# fmc-interposer.net
KiCad netlist of a schematic drawn in Altium Designer
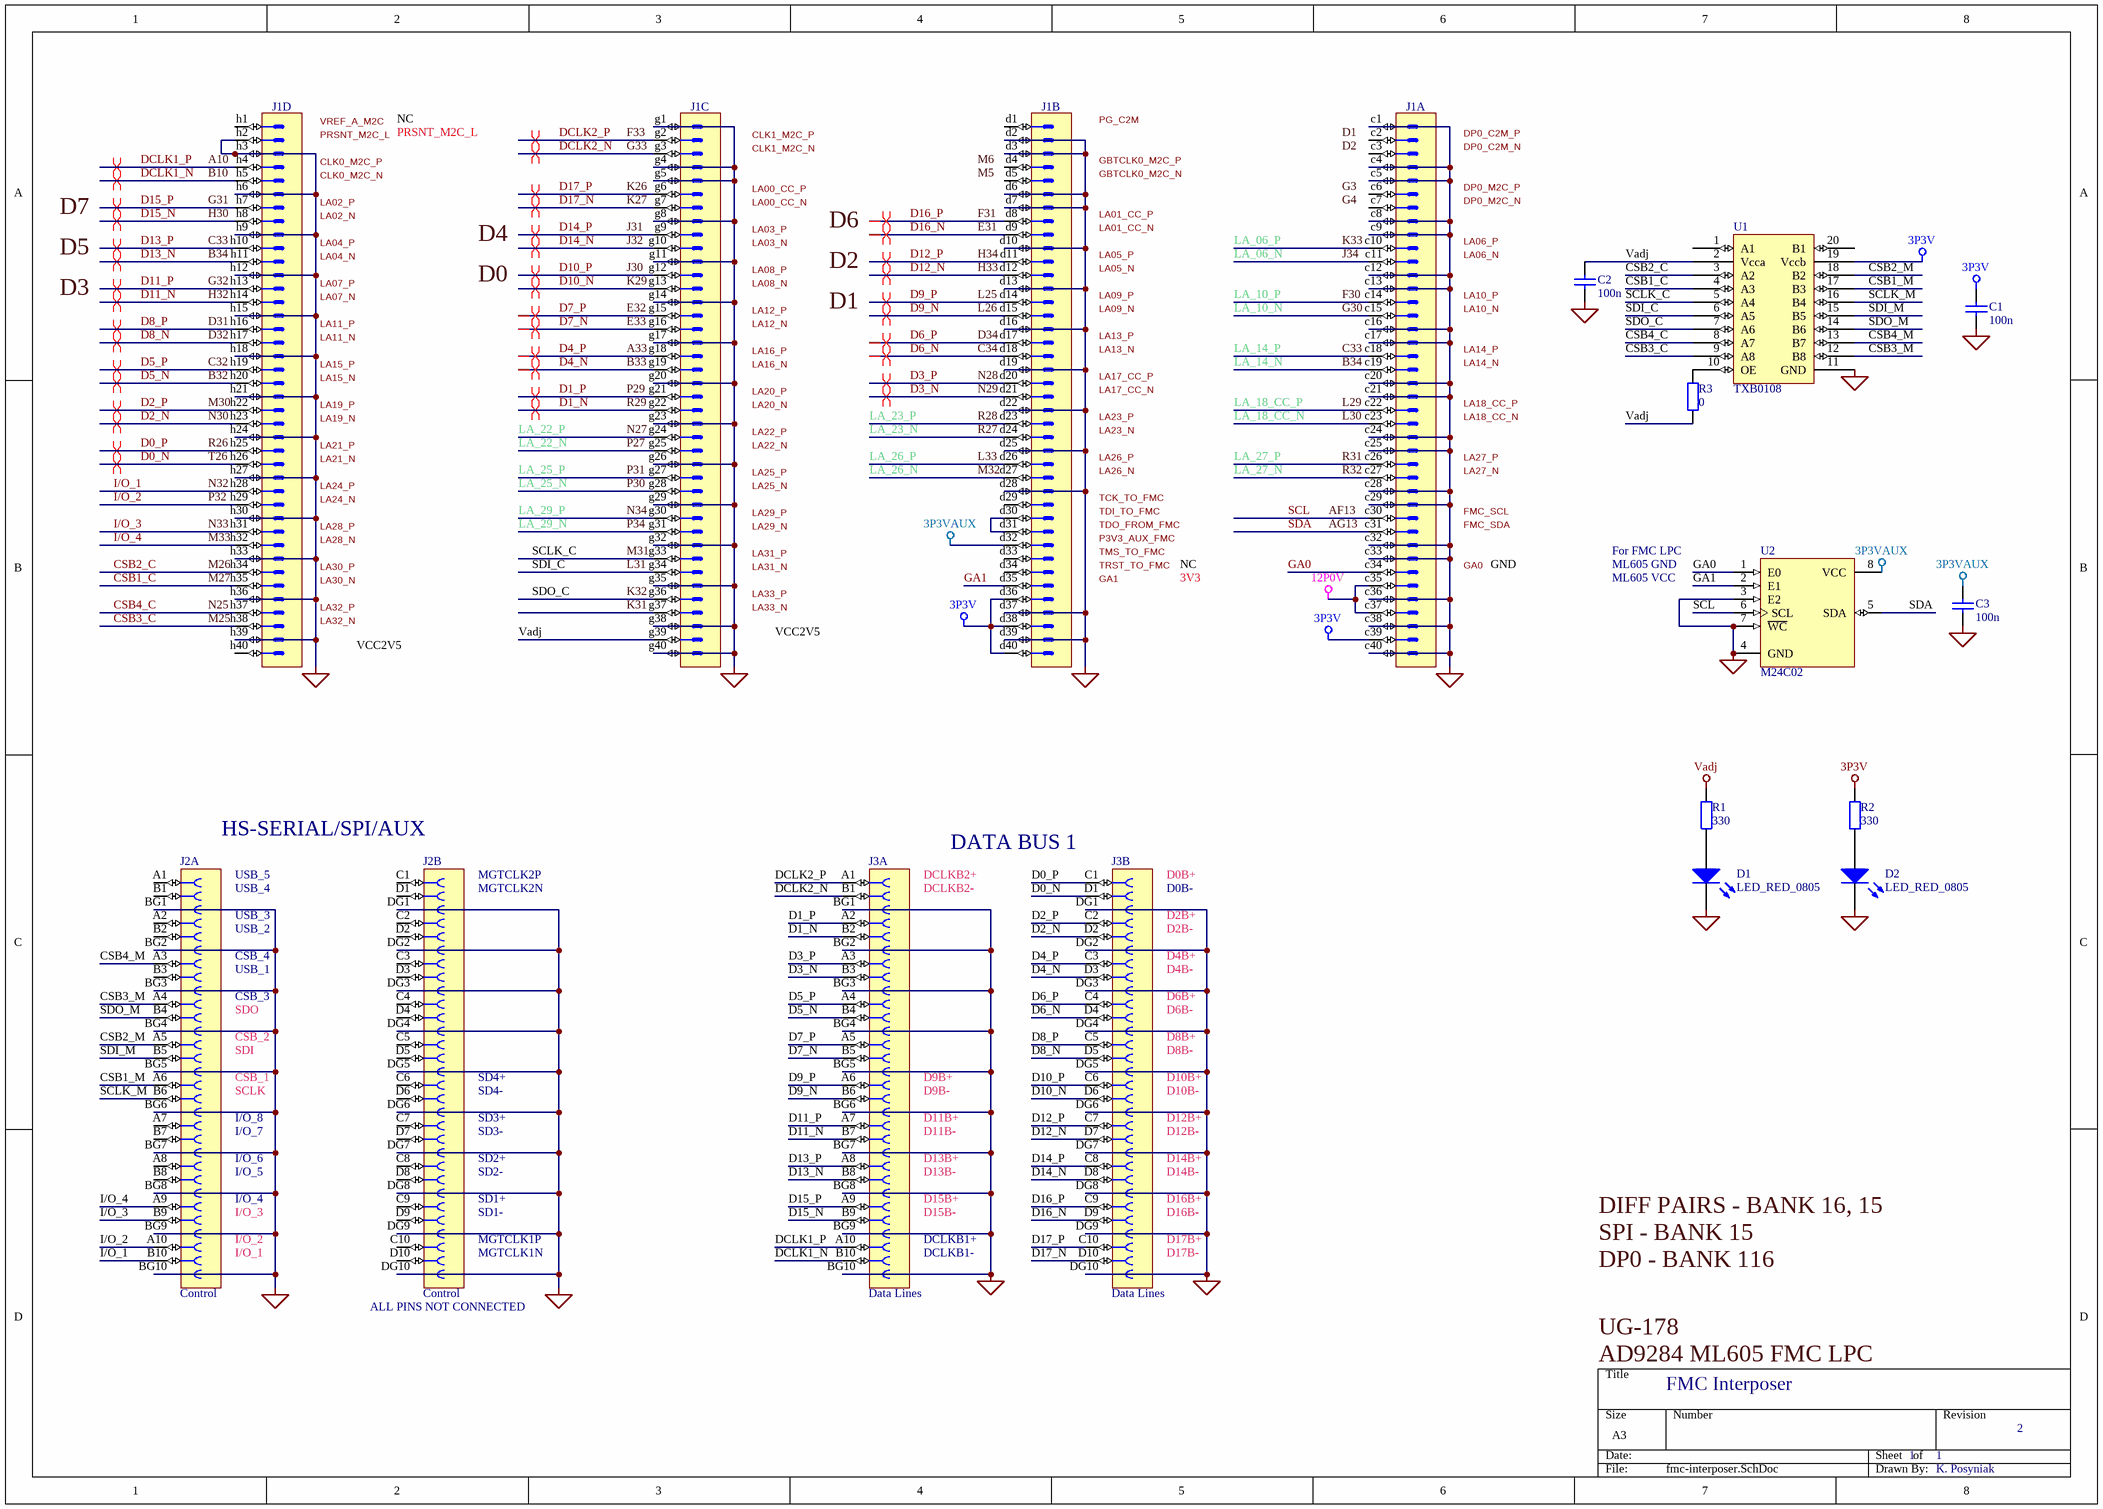
[diagram p0: fmc-interposer.SchDoc]

(export (version "E")
  (design (tool "Eeschema 10.0.6"))
  (components
    (comp (ref "C1")
      (value "100n")
      (footprint "capc1608n")
      (description "Capacitor")
      (fields (field (name "PUBLISHER") "Altium Limited"))
      (libsource (lib "Miscellaneous Devices") (part "Cap"))
    )
    (comp (ref "C2")
      (value "100n")
      (footprint "capc1608n")
      (description "Capacitor")
      (fields (field (name "PUBLISHER") "Altium Limited"))
      (libsource (lib "Miscellaneous Devices") (part "Cap"))
    )
    (comp (ref "C3")
      (value "100n")
      (footprint "capc1608n")
      (description "Capacitor")
      (fields (field (name "PUBLISHER") "Altium Limited"))
      (libsource (lib "Miscellaneous Devices") (part "Cap"))
    )
    (comp (ref "D1")
      (value "LED_RED_0805")
      (footprint "2.0X1.25X0.8")
      (description "Blue Surface Mount Chip LED, Blue")
      (fields (field (name "PUBLISHER") "Altium Limited"))
      (libsource (lib "Agilent Optoelectronic LED") (part "HSMB-C170"))
    )
    (comp (ref "D2")
      (value "LED_RED_0805")
      (footprint "2.0X1.25X0.8")
      (description "Blue Surface Mount Chip LED, Blue")
      (fields (field (name "PUBLISHER") "Altium Limited"))
      (libsource (lib "Agilent Optoelectronic LED") (part "HSMB-C170"))
    )
    (comp (ref "J1")
      (value "VITA 57")
      (footprint "SAMTEC_ASP-127797-01")
      (description "Connector VITA 57, 160 Male contacts in 4 row cdgh")
      (fields
        (field (name "PART NUMBER") "SAMTEC_ASP-127797-01")
        (field (name "MANUFACTURER") "SAMTEC")
        (field (name "AUTHOR") "CERN DEM JLC")
      )
      (libsource (lib "EDA-02408-V1") (part "Connector VITA 57 160 Male (cdgh)"))
    )
    (comp (ref "J2")
      (value "Control")
      (footprint "Analog_Conn2")
      (libsource (lib "kpos-sch") (part "Analog_Conn2"))
    )
    (comp (ref "J3")
      (value "Data Lines")
      (footprint "Analog_Conn2")
      (libsource (lib "kpos-sch") (part "Analog_Conn2"))
    )
    (comp (ref "R1")
      (value "330")
      (description "Resistor")
      (fields (field (name "PUBLISHER") "Altium Limited"))
      (libsource (lib "") (part "Res2_1"))
    )
    (comp (ref "R2")
      (value "330")
      (description "Resistor")
      (fields (field (name "PUBLISHER") "Altium Limited"))
      (libsource (lib "") (part "Res2_1"))
    )
    (comp (ref "R3")
      (value "0")
      (description "Resistor")
      (fields (field (name "PUBLISHER") "Altium Limited"))
      (libsource (lib "Miscellaneous Devices") (part "Res2"))
    )
    (comp (ref "U1") (value "TXB0108") (footprint "TSSOP20") (libsource (lib "kpos-sch") (part "TXB0108")))
    (comp (ref "U2")
      (value "M24C02")
      (footprint "SOP8_N")
      (description "2Kbit Serial I˛C Bus EEPROM")
      (fields (field (name "PUBLISHER") "Altium Limited"))
      (libsource (lib "ST Memory EEPROM Serial") (part "M24C02MN6"))
    )
  )
  (nets
    (net (code "1") (name "/CSB1_C") (class "Default")
      (node (ref "J1") (pin "h35") (pinfunction "h35_h35") (pintype "bidirectional"))
      (node (ref "U1") (pin "4") (pinfunction "A3_4") (pintype "bidirectional"))
    )
    (net (code "2") (name "/CSB1_M") (class "Default")
      (node (ref "J2") (pin "A6") (pinfunction "A6_A6") (pintype "bidirectional"))
      (node (ref "U1") (pin "17") (pinfunction "B3_17") (pintype "bidirectional"))
    )
    (net (code "3") (name "/CSB2_C") (class "Default")
      (node (ref "J1") (pin "h34") (pinfunction "h34_h34") (pintype "bidirectional"))
      (node (ref "U1") (pin "3") (pinfunction "A2_3") (pintype "bidirectional"))
    )
    (net (code "4") (name "/CSB2_M") (class "Default")
      (node (ref "J2") (pin "A5") (pinfunction "A5_A5") (pintype "bidirectional"))
      (node (ref "U1") (pin "18") (pinfunction "B2_18") (pintype "bidirectional"))
    )
    (net (code "5") (name "/CSB3_C") (class "Default")
      (node (ref "J1") (pin "h38") (pinfunction "h38_h38") (pintype "bidirectional"))
      (node (ref "U1") (pin "9") (pinfunction "A8_9") (pintype "bidirectional"))
    )
    (net (code "6") (name "/CSB3_M") (class "Default")
      (node (ref "J2") (pin "A4") (pinfunction "A4_A4") (pintype "bidirectional"))
      (node (ref "U1") (pin "12") (pinfunction "B8_12") (pintype "bidirectional"))
    )
    (net (code "7") (name "/CSB4_C") (class "Default")
      (node (ref "J1") (pin "h37") (pinfunction "h37_h37") (pintype "bidirectional"))
      (node (ref "U1") (pin "8") (pinfunction "A7_8") (pintype "bidirectional"))
    )
    (net (code "8") (name "/CSB4_M") (class "Default")
      (node (ref "J2") (pin "A3") (pinfunction "A3_A3") (pintype "bidirectional"))
      (node (ref "U1") (pin "13") (pinfunction "B7_13") (pintype "bidirectional"))
    )
    (net (code "9") (name "/D0_N") (class "Default")
      (node (ref "J1") (pin "h26") (pinfunction "h26_h26") (pintype "bidirectional"))
      (node (ref "J3") (pin "D1") (pinfunction "D1_D1") (pintype "bidirectional"))
    )
    (net (code "10") (name "/D0_P") (class "Default")
      (node (ref "J1") (pin "h25") (pinfunction "h25_h25") (pintype "bidirectional"))
      (node (ref "J3") (pin "C1") (pinfunction "C1_C1") (pintype "bidirectional"))
    )
    (net (code "11") (name "/D1_N") (class "Default")
      (node (ref "J1") (pin "g22") (pinfunction "g22_g22") (pintype "bidirectional"))
      (node (ref "J3") (pin "B2") (pinfunction "B2_B2") (pintype "bidirectional"))
    )
    (net (code "12") (name "/D1_P") (class "Default")
      (node (ref "J1") (pin "g21") (pinfunction "g21_g21") (pintype "bidirectional"))
      (node (ref "J3") (pin "A2") (pinfunction "A2_A2") (pintype "bidirectional"))
    )
    (net (code "13") (name "/D2_N") (class "Default")
      (node (ref "J1") (pin "h23") (pinfunction "h23_h23") (pintype "bidirectional"))
      (node (ref "J3") (pin "D2") (pinfunction "D2_D2") (pintype "bidirectional"))
    )
    (net (code "14") (name "/D2_P") (class "Default")
      (node (ref "J1") (pin "h22") (pinfunction "h22_h22") (pintype "bidirectional"))
      (node (ref "J3") (pin "C2") (pinfunction "C2_C2") (pintype "bidirectional"))
    )
    (net (code "15") (name "/D3_N") (class "Default")
      (node (ref "J1") (pin "d21") (pinfunction "d21_d21") (pintype "bidirectional"))
      (node (ref "J3") (pin "B3") (pinfunction "B3_B3") (pintype "bidirectional"))
    )
    (net (code "16") (name "/D3_P") (class "Default")
      (node (ref "J1") (pin "d20") (pinfunction "d20_d20") (pintype "bidirectional"))
      (node (ref "J3") (pin "A3") (pinfunction "A3_A3") (pintype "bidirectional"))
    )
    (net (code "17") (name "/D4_N") (class "Default")
      (node (ref "J1") (pin "g19") (pinfunction "g19_g19") (pintype "bidirectional"))
      (node (ref "J3") (pin "D3") (pinfunction "D3_D3") (pintype "bidirectional"))
    )
    (net (code "18") (name "/D4_P") (class "Default")
      (node (ref "J1") (pin "g18") (pinfunction "g18_g18") (pintype "bidirectional"))
      (node (ref "J3") (pin "C3") (pinfunction "C3_C3") (pintype "bidirectional"))
    )
    (net (code "19") (name "/D5_N") (class "Default")
      (node (ref "J1") (pin "h20") (pinfunction "h20_h20") (pintype "bidirectional"))
      (node (ref "J3") (pin "B4") (pinfunction "B4_B4") (pintype "bidirectional"))
    )
    (net (code "20") (name "/D5_P") (class "Default")
      (node (ref "J1") (pin "h19") (pinfunction "h19_h19") (pintype "bidirectional"))
      (node (ref "J3") (pin "A4") (pinfunction "A4_A4") (pintype "bidirectional"))
    )
    (net (code "21") (name "/D6_N") (class "Default")
      (node (ref "J1") (pin "d18") (pinfunction "d18_d18") (pintype "bidirectional"))
      (node (ref "J3") (pin "D4") (pinfunction "D4_D4") (pintype "bidirectional"))
    )
    (net (code "22") (name "/D6_P") (class "Default")
      (node (ref "J1") (pin "d17") (pinfunction "d17_d17") (pintype "bidirectional"))
      (node (ref "J3") (pin "C4") (pinfunction "C4_C4") (pintype "bidirectional"))
    )
    (net (code "23") (name "/D7_N") (class "Default")
      (node (ref "J1") (pin "g16") (pinfunction "g16_g16") (pintype "bidirectional"))
      (node (ref "J3") (pin "B5") (pinfunction "B5_B5") (pintype "bidirectional"))
    )
    (net (code "24") (name "/D7_P") (class "Default")
      (node (ref "J1") (pin "g15") (pinfunction "g15_g15") (pintype "bidirectional"))
      (node (ref "J3") (pin "A5") (pinfunction "A5_A5") (pintype "bidirectional"))
    )
    (net (code "25") (name "/D8_N") (class "Default")
      (node (ref "J1") (pin "h17") (pinfunction "h17_h17") (pintype "bidirectional"))
      (node (ref "J3") (pin "D5") (pinfunction "D5_D5") (pintype "bidirectional"))
    )
    (net (code "26") (name "/D8_P") (class "Default")
      (node (ref "J1") (pin "h16") (pinfunction "h16_h16") (pintype "bidirectional"))
      (node (ref "J3") (pin "C5") (pinfunction "C5_C5") (pintype "bidirectional"))
    )
    (net (code "27") (name "/D9_N") (class "Default")
      (node (ref "J1") (pin "d15") (pinfunction "d15_d15") (pintype "bidirectional"))
      (node (ref "J3") (pin "B6") (pinfunction "B6_B6") (pintype "bidirectional"))
    )
    (net (code "28") (name "/D9_P") (class "Default")
      (node (ref "J1") (pin "d14") (pinfunction "d14_d14") (pintype "bidirectional"))
      (node (ref "J3") (pin "A6") (pinfunction "A6_A6") (pintype "bidirectional"))
    )
    (net (code "29") (name "/D10_N") (class "Default")
      (node (ref "J1") (pin "g13") (pinfunction "g13_g13") (pintype "bidirectional"))
      (node (ref "J3") (pin "D6") (pinfunction "D6_D6") (pintype "bidirectional"))
    )
    (net (code "30") (name "/D10_P") (class "Default")
      (node (ref "J1") (pin "g12") (pinfunction "g12_g12") (pintype "bidirectional"))
      (node (ref "J3") (pin "C6") (pinfunction "C6_C6") (pintype "bidirectional"))
    )
    (net (code "31") (name "/D11_N") (class "Default")
      (node (ref "J1") (pin "h14") (pinfunction "h14_h14") (pintype "bidirectional"))
      (node (ref "J3") (pin "B7") (pinfunction "B7_B7") (pintype "bidirectional"))
    )
    (net (code "32") (name "/D11_P") (class "Default")
      (node (ref "J1") (pin "h13") (pinfunction "h13_h13") (pintype "bidirectional"))
      (node (ref "J3") (pin "A7") (pinfunction "A7_A7") (pintype "bidirectional"))
    )
    (net (code "33") (name "/D12_N") (class "Default")
      (node (ref "J1") (pin "d12") (pinfunction "d12_d12") (pintype "bidirectional"))
      (node (ref "J3") (pin "D7") (pinfunction "D7_D7") (pintype "bidirectional"))
    )
    (net (code "34") (name "/D12_P") (class "Default")
      (node (ref "J1") (pin "d11") (pinfunction "d11_d11") (pintype "bidirectional"))
      (node (ref "J3") (pin "C7") (pinfunction "C7_C7") (pintype "bidirectional"))
    )
    (net (code "35") (name "/D13_N") (class "Default")
      (node (ref "J1") (pin "h11") (pinfunction "h11_h11") (pintype "bidirectional"))
      (node (ref "J3") (pin "B8") (pinfunction "B8_B8") (pintype "bidirectional"))
    )
    (net (code "36") (name "/D13_P") (class "Default")
      (node (ref "J1") (pin "h10") (pinfunction "h10_h10") (pintype "bidirectional"))
      (node (ref "J3") (pin "A8") (pinfunction "A8_A8") (pintype "bidirectional"))
    )
    (net (code "37") (name "/D14_N") (class "Default")
      (node (ref "J1") (pin "g10") (pinfunction "g10_g10") (pintype "bidirectional"))
      (node (ref "J3") (pin "D8") (pinfunction "D8_D8") (pintype "bidirectional"))
    )
    (net (code "38") (name "/D14_P") (class "Default")
      (node (ref "J1") (pin "g9") (pinfunction "g9_g9") (pintype "bidirectional"))
      (node (ref "J3") (pin "C8") (pinfunction "C8_C8") (pintype "bidirectional"))
    )
    (net (code "39") (name "/D15_N") (class "Default")
      (node (ref "J1") (pin "h8") (pinfunction "h8_h8") (pintype "bidirectional"))
      (node (ref "J3") (pin "B9") (pinfunction "B9_B9") (pintype "bidirectional"))
    )
    (net (code "40") (name "/D15_P") (class "Default")
      (node (ref "J1") (pin "h7") (pinfunction "h7_h7") (pintype "bidirectional"))
      (node (ref "J3") (pin "A9") (pinfunction "A9_A9") (pintype "bidirectional"))
    )
    (net (code "41") (name "/D16_N") (class "Default")
      (node (ref "J1") (pin "d9") (pinfunction "d9_d9") (pintype "bidirectional"))
      (node (ref "J3") (pin "D9") (pinfunction "D9_D9") (pintype "bidirectional"))
    )
    (net (code "42") (name "/D16_P") (class "Default")
      (node (ref "J1") (pin "d8") (pinfunction "d8_d8") (pintype "bidirectional"))
      (node (ref "J3") (pin "C9") (pinfunction "C9_C9") (pintype "bidirectional"))
    )
    (net (code "43") (name "/D17_N") (class "Default")
      (node (ref "J1") (pin "g7") (pinfunction "g7_g7") (pintype "bidirectional"))
      (node (ref "J3") (pin "D10") (pinfunction "D10_D10") (pintype "bidirectional"))
    )
    (net (code "44") (name "/D17_P") (class "Default")
      (node (ref "J1") (pin "g6") (pinfunction "g6_g6") (pintype "bidirectional"))
      (node (ref "J3") (pin "C10") (pinfunction "C10_C10") (pintype "bidirectional"))
    )
    (net (code "45") (name "/DCLK1_N") (class "Default")
      (node (ref "J1") (pin "h5") (pinfunction "h5_h5") (pintype "bidirectional"))
      (node (ref "J3") (pin "B10") (pinfunction "B10_B10") (pintype "bidirectional"))
    )
    (net (code "46") (name "/DCLK1_P") (class "Default")
      (node (ref "J1") (pin "h4") (pinfunction "h4_h4") (pintype "bidirectional"))
      (node (ref "J3") (pin "A10") (pinfunction "A10_A10") (pintype "bidirectional"))
    )
    (net (code "47") (name "/DCLK2_N") (class "Default")
      (node (ref "J1") (pin "g3") (pinfunction "g3_g3") (pintype "bidirectional"))
      (node (ref "J3") (pin "B1") (pinfunction "B1_B1") (pintype "bidirectional"))
    )
    (net (code "48") (name "/DCLK2_P") (class "Default")
      (node (ref "J1") (pin "g2") (pinfunction "g2_g2") (pintype "bidirectional"))
      (node (ref "J3") (pin "A1") (pinfunction "A1_A1") (pintype "bidirectional"))
    )
    (net (code "49") (name "/GA0") (class "Default")
      (node (ref "J1") (pin "c34") (pinfunction "c34_c34") (pintype "bidirectional"))
      (node (ref "U2") (pin "1") (pinfunction "E0_1") (pintype "input"))
    )
    (net (code "50") (name "/GA1") (class "Default")
      (node (ref "J1") (pin "d35") (pinfunction "d35_d35") (pintype "bidirectional"))
      (node (ref "U2") (pin "2") (pinfunction "E1_2") (pintype "input"))
    )
    (net (code "51") (name "/I{slash}O_1") (class "Default")
      (node (ref "J1") (pin "h28") (pinfunction "h28_h28") (pintype "bidirectional"))
      (node (ref "J2") (pin "B10") (pinfunction "B10_B10") (pintype "bidirectional"))
    )
    (net (code "52") (name "/I{slash}O_2") (class "Default")
      (node (ref "J1") (pin "h29") (pinfunction "h29_h29") (pintype "bidirectional"))
      (node (ref "J2") (pin "A10") (pinfunction "A10_A10") (pintype "bidirectional"))
    )
    (net (code "53") (name "/I{slash}O_3") (class "Default")
      (node (ref "J1") (pin "h31") (pinfunction "h31_h31") (pintype "bidirectional"))
      (node (ref "J2") (pin "B9") (pinfunction "B9_B9") (pintype "bidirectional"))
    )
    (net (code "54") (name "/I{slash}O_4") (class "Default")
      (node (ref "J1") (pin "h32") (pinfunction "h32_h32") (pintype "bidirectional"))
      (node (ref "J2") (pin "A9") (pinfunction "A9_A9") (pintype "bidirectional"))
    )
    (net (code "55") (name "/LA_06_N") (class "Default")
      (node (ref "J1") (pin "c11") (pinfunction "c11_c11") (pintype "bidirectional"))
    )
    (net (code "56") (name "/LA_06_P") (class "Default")
      (node (ref "J1") (pin "c10") (pinfunction "c10_c10") (pintype "bidirectional"))
    )
    (net (code "57") (name "/LA_10_N") (class "Default")
      (node (ref "J1") (pin "c15") (pinfunction "c15_c15") (pintype "bidirectional"))
    )
    (net (code "58") (name "/LA_10_P") (class "Default")
      (node (ref "J1") (pin "c14") (pinfunction "c14_c14") (pintype "bidirectional"))
    )
    (net (code "59") (name "/LA_14_N") (class "Default")
      (node (ref "J1") (pin "c19") (pinfunction "c19_c19") (pintype "bidirectional"))
    )
    (net (code "60") (name "/LA_14_P") (class "Default")
      (node (ref "J1") (pin "c18") (pinfunction "c18_c18") (pintype "bidirectional"))
    )
    (net (code "61") (name "/LA_18_CC_N") (class "Default")
      (node (ref "J1") (pin "c23") (pinfunction "c23_c23") (pintype "bidirectional"))
    )
    (net (code "62") (name "/LA_18_CC_P") (class "Default")
      (node (ref "J1") (pin "c22") (pinfunction "c22_c22") (pintype "bidirectional"))
    )
    (net (code "63") (name "/LA_22_N") (class "Default")
      (node (ref "J1") (pin "g25") (pinfunction "g25_g25") (pintype "bidirectional"))
    )
    (net (code "64") (name "/LA_22_P") (class "Default")
      (node (ref "J1") (pin "g24") (pinfunction "g24_g24") (pintype "bidirectional"))
    )
    (net (code "65") (name "/LA_23_N") (class "Default")
      (node (ref "J1") (pin "d24") (pinfunction "d24_d24") (pintype "bidirectional"))
    )
    (net (code "66") (name "/LA_23_P") (class "Default")
      (node (ref "J1") (pin "d23") (pinfunction "d23_d23") (pintype "bidirectional"))
    )
    (net (code "67") (name "/LA_25_N") (class "Default")
      (node (ref "J1") (pin "g28") (pinfunction "g28_g28") (pintype "bidirectional"))
    )
    (net (code "68") (name "/LA_25_P") (class "Default")
      (node (ref "J1") (pin "g27") (pinfunction "g27_g27") (pintype "bidirectional"))
    )
    (net (code "69") (name "/LA_26_N") (class "Default")
      (node (ref "J1") (pin "d27") (pinfunction "d27_d27") (pintype "bidirectional"))
    )
    (net (code "70") (name "/LA_26_P") (class "Default")
      (node (ref "J1") (pin "d26") (pinfunction "d26_d26") (pintype "bidirectional"))
    )
    (net (code "71") (name "/LA_27_N") (class "Default")
      (node (ref "J1") (pin "c27") (pinfunction "c27_c27") (pintype "bidirectional"))
    )
    (net (code "72") (name "/LA_27_P") (class "Default")
      (node (ref "J1") (pin "c26") (pinfunction "c26_c26") (pintype "bidirectional"))
    )
    (net (code "73") (name "/LA_29_N") (class "Default")
      (node (ref "J1") (pin "g31") (pinfunction "g31_g31") (pintype "bidirectional"))
    )
    (net (code "74") (name "/LA_29_P") (class "Default")
      (node (ref "J1") (pin "g30") (pinfunction "g30_g30") (pintype "bidirectional"))
    )
    (net (code "75") (name "/SCL") (class "Default")
      (node (ref "J1") (pin "c30") (pinfunction "c30_c30") (pintype "bidirectional"))
      (node (ref "U2") (pin "6") (pinfunction "SCL_6") (pintype "input"))
    )
    (net (code "76") (name "/SCLK_C") (class "Default")
      (node (ref "J1") (pin "g33") (pinfunction "g33_g33") (pintype "bidirectional"))
      (node (ref "U1") (pin "5") (pinfunction "A4_5") (pintype "bidirectional"))
    )
    (net (code "77") (name "/SCLK_M") (class "Default")
      (node (ref "J2") (pin "B6") (pinfunction "B6_B6") (pintype "bidirectional"))
      (node (ref "U1") (pin "16") (pinfunction "B4_16") (pintype "bidirectional"))
    )
    (net (code "78") (name "/SDA") (class "Default")
      (node (ref "J1") (pin "c31") (pinfunction "c31_c31") (pintype "bidirectional"))
      (node (ref "U2") (pin "5") (pinfunction "SDA_5") (pintype "bidirectional"))
    )
    (net (code "79") (name "/SDI_C") (class "Default")
      (node (ref "J1") (pin "g34") (pinfunction "g34_g34") (pintype "bidirectional"))
      (node (ref "U1") (pin "6") (pinfunction "A5_6") (pintype "bidirectional"))
    )
    (net (code "80") (name "/SDI_M") (class "Default")
      (node (ref "J2") (pin "B5") (pinfunction "B5_B5") (pintype "bidirectional"))
      (node (ref "U1") (pin "15") (pinfunction "B5_15") (pintype "bidirectional"))
    )
    (net (code "81") (name "/SDO_C") (class "Default")
      (node (ref "J1") (pin "g36") (pinfunction "g36_g36") (pintype "bidirectional"))
      (node (ref "U1") (pin "7") (pinfunction "A6_7") (pintype "bidirectional"))
    )
    (net (code "82") (name "/SDO_M") (class "Default")
      (node (ref "J2") (pin "B4") (pinfunction "B4_B4") (pintype "bidirectional"))
      (node (ref "U1") (pin "14") (pinfunction "B6_14") (pintype "bidirectional"))
    )
    (net (code "83") (name "3P3V") (class "Default")
      (node (ref "C1") (pin "2") (pinfunction "2_2") (pintype "passive"))
      (node (ref "J1") (pin "c39") (pinfunction "c39_c39") (pintype "bidirectional"))
      (node (ref "J1") (pin "d36") (pinfunction "d36_d36") (pintype "bidirectional"))
      (node (ref "J1") (pin "d38") (pinfunction "d38_d38") (pintype "bidirectional"))
      (node (ref "J1") (pin "d40") (pinfunction "d40_d40") (pintype "bidirectional"))
      (node (ref "R2") (pin "2") (pinfunction "2_2") (pintype "passive"))
      (node (ref "U1") (pin "19") (pinfunction "Vccb_19") (pintype "power_in"))
    )
    (net (code "84") (name "3P3VAUX") (class "Default")
      (node (ref "C3") (pin "2") (pinfunction "2_2") (pintype "passive"))
      (node (ref "J1") (pin "d32") (pinfunction "d32_d32") (pintype "bidirectional"))
      (node (ref "U2") (pin "8") (pinfunction "VCC_8") (pintype "power_in"))
    )
    (net (code "85") (name "12P0V") (class "Default")
      (node (ref "J1") (pin "c35") (pinfunction "c35_c35") (pintype "bidirectional"))
      (node (ref "J1") (pin "c37") (pinfunction "c37_c37") (pintype "bidirectional"))
    )
    (net (code "86") (name "GND") (class "Default")
      (node (ref "C1") (pin "1") (pinfunction "1_1") (pintype "passive"))
      (node (ref "C2") (pin "1") (pinfunction "1_1") (pintype "passive"))
      (node (ref "C3") (pin "1") (pinfunction "1_1") (pintype "passive"))
      (node (ref "D1") (pin "2") (pinfunction "K_2") (pintype "passive"))
      (node (ref "D2") (pin "2") (pinfunction "K_2") (pintype "passive"))
      (node (ref "J1") (pin "c1") (pinfunction "c1_c1") (pintype "bidirectional"))
      (node (ref "J1") (pin "c12") (pinfunction "c12_c12") (pintype "bidirectional"))
      (node (ref "J1") (pin "c13") (pinfunction "c13_c13") (pintype "bidirectional"))
      (node (ref "J1") (pin "c16") (pinfunction "c16_c16") (pintype "bidirectional"))
      (node (ref "J1") (pin "c17") (pinfunction "c17_c17") (pintype "bidirectional"))
      (node (ref "J1") (pin "c20") (pinfunction "c20_c20") (pintype "bidirectional"))
      (node (ref "J1") (pin "c21") (pinfunction "c21_c21") (pintype "bidirectional"))
      (node (ref "J1") (pin "c24") (pinfunction "c24_c24") (pintype "bidirectional"))
      (node (ref "J1") (pin "c25") (pinfunction "c25_c25") (pintype "bidirectional"))
      (node (ref "J1") (pin "c28") (pinfunction "c28_c28") (pintype "bidirectional"))
      (node (ref "J1") (pin "c29") (pinfunction "c29_c29") (pintype "bidirectional"))
      (node (ref "J1") (pin "c32") (pinfunction "c32_c32") (pintype "bidirectional"))
      (node (ref "J1") (pin "c33") (pinfunction "c33_c33") (pintype "bidirectional"))
      (node (ref "J1") (pin "c36") (pinfunction "c36_c36") (pintype "bidirectional"))
      (node (ref "J1") (pin "c38") (pinfunction "c38_c38") (pintype "bidirectional"))
      (node (ref "J1") (pin "c4") (pinfunction "c4_c4") (pintype "bidirectional"))
      (node (ref "J1") (pin "c40") (pinfunction "c40_c40") (pintype "bidirectional"))
      (node (ref "J1") (pin "c5") (pinfunction "c5_c5") (pintype "bidirectional"))
      (node (ref "J1") (pin "c8") (pinfunction "c8_c8") (pintype "bidirectional"))
      (node (ref "J1") (pin "c9") (pinfunction "c9_c9") (pintype "bidirectional"))
      (node (ref "J1") (pin "d10") (pinfunction "d10_d10") (pintype "bidirectional"))
      (node (ref "J1") (pin "d13") (pinfunction "d13_d13") (pintype "bidirectional"))
      (node (ref "J1") (pin "d16") (pinfunction "d16_d16") (pintype "bidirectional"))
      (node (ref "J1") (pin "d19") (pinfunction "d19_d19") (pintype "bidirectional"))
      (node (ref "J1") (pin "d2") (pinfunction "d2_d2") (pintype "bidirectional"))
      (node (ref "J1") (pin "d22") (pinfunction "d22_d22") (pintype "bidirectional"))
      (node (ref "J1") (pin "d25") (pinfunction "d25_d25") (pintype "bidirectional"))
      (node (ref "J1") (pin "d28") (pinfunction "d28_d28") (pintype "bidirectional"))
      (node (ref "J1") (pin "d3") (pinfunction "d3_d3") (pintype "bidirectional"))
      (node (ref "J1") (pin "d37") (pinfunction "d37_d37") (pintype "bidirectional"))
      (node (ref "J1") (pin "d39") (pinfunction "d39_d39") (pintype "bidirectional"))
      (node (ref "J1") (pin "d6") (pinfunction "d6_d6") (pintype "bidirectional"))
      (node (ref "J1") (pin "d7") (pinfunction "d7_d7") (pintype "bidirectional"))
      (node (ref "J1") (pin "g1") (pinfunction "g1_g1") (pintype "bidirectional"))
      (node (ref "J1") (pin "g11") (pinfunction "g11_g11") (pintype "bidirectional"))
      (node (ref "J1") (pin "g14") (pinfunction "g14_g14") (pintype "bidirectional"))
      (node (ref "J1") (pin "g17") (pinfunction "g17_g17") (pintype "bidirectional"))
      (node (ref "J1") (pin "g20") (pinfunction "g20_g20") (pintype "bidirectional"))
      (node (ref "J1") (pin "g23") (pinfunction "g23_g23") (pintype "bidirectional"))
      (node (ref "J1") (pin "g26") (pinfunction "g26_g26") (pintype "bidirectional"))
      (node (ref "J1") (pin "g29") (pinfunction "g29_g29") (pintype "bidirectional"))
      (node (ref "J1") (pin "g32") (pinfunction "g32_g32") (pintype "bidirectional"))
      (node (ref "J1") (pin "g35") (pinfunction "g35_g35") (pintype "bidirectional"))
      (node (ref "J1") (pin "g38") (pinfunction "g38_g38") (pintype "bidirectional"))
      (node (ref "J1") (pin "g4") (pinfunction "g4_g4") (pintype "bidirectional"))
      (node (ref "J1") (pin "g40") (pinfunction "g40_g40") (pintype "bidirectional"))
      (node (ref "J1") (pin "g5") (pinfunction "g5_g5") (pintype "bidirectional"))
      (node (ref "J1") (pin "g8") (pinfunction "g8_g8") (pintype "bidirectional"))
      (node (ref "J1") (pin "h12") (pinfunction "h12_h12") (pintype "bidirectional"))
      (node (ref "J1") (pin "h15") (pinfunction "h15_h15") (pintype "bidirectional"))
      (node (ref "J1") (pin "h18") (pinfunction "h18_h18") (pintype "bidirectional"))
      (node (ref "J1") (pin "h2") (pinfunction "h2_h2") (pintype "bidirectional"))
      (node (ref "J1") (pin "h21") (pinfunction "h21_h21") (pintype "bidirectional"))
      (node (ref "J1") (pin "h24") (pinfunction "h24_h24") (pintype "bidirectional"))
      (node (ref "J1") (pin "h27") (pinfunction "h27_h27") (pintype "bidirectional"))
      (node (ref "J1") (pin "h3") (pinfunction "h3_h3") (pintype "bidirectional"))
      (node (ref "J1") (pin "h30") (pinfunction "h30_h30") (pintype "bidirectional"))
      (node (ref "J1") (pin "h33") (pinfunction "h33_h33") (pintype "bidirectional"))
      (node (ref "J1") (pin "h36") (pinfunction "h36_h36") (pintype "bidirectional"))
      (node (ref "J1") (pin "h39") (pinfunction "h39_h39") (pintype "bidirectional"))
      (node (ref "J1") (pin "h6") (pinfunction "h6_h6") (pintype "bidirectional"))
      (node (ref "J1") (pin "h9") (pinfunction "h9_h9") (pintype "bidirectional"))
      (node (ref "J2") (pin "BG1") (pinfunction "BG1_BG1") (pintype "power_in"))
      (node (ref "J2") (pin "BG10") (pinfunction "BG10_BG10") (pintype "power_in"))
      (node (ref "J2") (pin "BG2") (pinfunction "BG2_BG2") (pintype "power_in"))
      (node (ref "J2") (pin "BG3") (pinfunction "BG3_BG3") (pintype "power_in"))
      (node (ref "J2") (pin "BG4") (pinfunction "BG4_BG4") (pintype "power_in"))
      (node (ref "J2") (pin "BG5") (pinfunction "BG5_BG5") (pintype "power_in"))
      (node (ref "J2") (pin "BG6") (pinfunction "BG6_BG6") (pintype "power_in"))
      (node (ref "J2") (pin "BG7") (pinfunction "BG7_BG7") (pintype "power_in"))
      (node (ref "J2") (pin "BG8") (pinfunction "BG8_BG8") (pintype "power_in"))
      (node (ref "J2") (pin "BG9") (pinfunction "BG9_BG9") (pintype "power_in"))
      (node (ref "J2") (pin "DG1") (pinfunction "DG1_DG1") (pintype "power_in"))
      (node (ref "J2") (pin "DG10") (pinfunction "DG10_DG10") (pintype "power_in"))
      (node (ref "J2") (pin "DG2") (pinfunction "DG2_DG2") (pintype "power_in"))
      (node (ref "J2") (pin "DG3") (pinfunction "DG3_DG3") (pintype "power_in"))
      (node (ref "J2") (pin "DG4") (pinfunction "DG4_DG4") (pintype "power_in"))
      (node (ref "J2") (pin "DG5") (pinfunction "DG5_DG5") (pintype "power_in"))
      (node (ref "J2") (pin "DG6") (pinfunction "DG6_DG6") (pintype "power_in"))
      (node (ref "J2") (pin "DG7") (pinfunction "DG7_DG7") (pintype "power_in"))
      (node (ref "J2") (pin "DG8") (pinfunction "DG8_DG8") (pintype "power_in"))
      (node (ref "J2") (pin "DG9") (pinfunction "DG9_DG9") (pintype "power_in"))
      (node (ref "J3") (pin "BG1") (pinfunction "BG1_BG1") (pintype "power_in"))
      (node (ref "J3") (pin "BG10") (pinfunction "BG10_BG10") (pintype "power_in"))
      (node (ref "J3") (pin "BG2") (pinfunction "BG2_BG2") (pintype "power_in"))
      (node (ref "J3") (pin "BG3") (pinfunction "BG3_BG3") (pintype "power_in"))
      (node (ref "J3") (pin "BG4") (pinfunction "BG4_BG4") (pintype "power_in"))
      (node (ref "J3") (pin "BG5") (pinfunction "BG5_BG5") (pintype "power_in"))
      (node (ref "J3") (pin "BG6") (pinfunction "BG6_BG6") (pintype "power_in"))
      (node (ref "J3") (pin "BG7") (pinfunction "BG7_BG7") (pintype "power_in"))
      (node (ref "J3") (pin "BG8") (pinfunction "BG8_BG8") (pintype "power_in"))
      (node (ref "J3") (pin "BG9") (pinfunction "BG9_BG9") (pintype "power_in"))
      (node (ref "J3") (pin "DG1") (pinfunction "DG1_DG1") (pintype "power_in"))
      (node (ref "J3") (pin "DG10") (pinfunction "DG10_DG10") (pintype "power_in"))
      (node (ref "J3") (pin "DG2") (pinfunction "DG2_DG2") (pintype "power_in"))
      (node (ref "J3") (pin "DG3") (pinfunction "DG3_DG3") (pintype "power_in"))
      (node (ref "J3") (pin "DG4") (pinfunction "DG4_DG4") (pintype "power_in"))
      (node (ref "J3") (pin "DG5") (pinfunction "DG5_DG5") (pintype "power_in"))
      (node (ref "J3") (pin "DG6") (pinfunction "DG6_DG6") (pintype "power_in"))
      (node (ref "J3") (pin "DG7") (pinfunction "DG7_DG7") (pintype "power_in"))
      (node (ref "J3") (pin "DG8") (pinfunction "DG8_DG8") (pintype "power_in"))
      (node (ref "J3") (pin "DG9") (pinfunction "DG9_DG9") (pintype "power_in"))
      (node (ref "U1") (pin "11") (pinfunction "GND_11") (pintype "power_in"))
      (node (ref "U2") (pin "3") (pinfunction "E2_3") (pintype "input"))
      (node (ref "U2") (pin "4") (pinfunction "GND_4") (pintype "power_in"))
      (node (ref "U2") (pin "7") (pinfunction "~{WC}_7") (pintype "input"))
    )
    (net (code "87") (name "Net-(D1-A)") (class "Default")
      (node (ref "D1") (pin "1") (pinfunction "A_1") (pintype "passive"))
      (node (ref "R1") (pin "1") (pinfunction "1_1") (pintype "passive"))
    )
    (net (code "88") (name "Net-(D2-A)") (class "Default")
      (node (ref "D2") (pin "1") (pinfunction "A_1") (pintype "passive"))
      (node (ref "R2") (pin "1") (pinfunction "1_1") (pintype "passive"))
    )
    (net (code "89") (name "Net-(J1-Padd30)") (class "Default")
      (node (ref "J1") (pin "d30") (pinfunction "d30_d30") (pintype "bidirectional"))
      (node (ref "J1") (pin "d31") (pinfunction "d31_d31") (pintype "bidirectional"))
    )
    (net (code "90") (name "Net-(U1-OE)") (class "Default")
      (node (ref "R3") (pin "1") (pinfunction "1_1") (pintype "passive"))
      (node (ref "U1") (pin "10") (pinfunction "OE_10") (pintype "bidirectional"))
    )
    (net (code "91") (name "Vadj") (class "Default")
      (node (ref "C2") (pin "2") (pinfunction "2_2") (pintype "passive"))
      (node (ref "J1") (pin "g39") (pinfunction "g39_g39") (pintype "bidirectional"))
      (node (ref "R1") (pin "2") (pinfunction "2_2") (pintype "passive"))
      (node (ref "R3") (pin "2") (pinfunction "2_2") (pintype "passive"))
      (node (ref "U1") (pin "2") (pinfunction "Vcca_2") (pintype "power_in"))
    )
    (net (code "92") (name "unconnected-(J1-Padc2)") (class "Default")
      (node (ref "J1") (pin "c2") (pinfunction "c2_c2") (pintype "bidirectional"))
    )
    (net (code "93") (name "unconnected-(J1-Padc3)") (class "Default")
      (node (ref "J1") (pin "c3") (pinfunction "c3_c3") (pintype "bidirectional"))
    )
    (net (code "94") (name "unconnected-(J1-Padc6)") (class "Default")
      (node (ref "J1") (pin "c6") (pinfunction "c6_c6") (pintype "bidirectional"))
    )
    (net (code "95") (name "unconnected-(J1-Padc7)") (class "Default")
      (node (ref "J1") (pin "c7") (pinfunction "c7_c7") (pintype "bidirectional"))
    )
    (net (code "96") (name "unconnected-(J1-Padd1)") (class "Default")
      (node (ref "J1") (pin "d1") (pinfunction "d1_d1") (pintype "bidirectional"))
    )
    (net (code "97") (name "unconnected-(J1-Padd4)") (class "Default")
      (node (ref "J1") (pin "d4") (pinfunction "d4_d4") (pintype "bidirectional"))
    )
    (net (code "98") (name "unconnected-(J1-Padd5)") (class "Default")
      (node (ref "J1") (pin "d5") (pinfunction "d5_d5") (pintype "bidirectional"))
    )
    (net (code "99") (name "unconnected-(J1-Padd29)") (class "Default")
      (node (ref "J1") (pin "d29") (pinfunction "d29_d29") (pintype "bidirectional"))
    )
    (net (code "100") (name "unconnected-(J1-Padd33)") (class "Default")
      (node (ref "J1") (pin "d33") (pinfunction "d33_d33") (pintype "bidirectional"))
    )
    (net (code "101") (name "unconnected-(J1-Padd34)") (class "Default")
      (node (ref "J1") (pin "d34") (pinfunction "d34_d34") (pintype "bidirectional"))
    )
    (net (code "102") (name "unconnected-(J1-Padg37)") (class "Default")
      (node (ref "J1") (pin "g37") (pinfunction "g37_g37") (pintype "bidirectional"))
    )
    (net (code "103") (name "unconnected-(J1-Padh1)") (class "Default")
      (node (ref "J1") (pin "h1") (pinfunction "h1_h1") (pintype "bidirectional"))
    )
    (net (code "104") (name "unconnected-(J1-Padh40)") (class "Default")
      (node (ref "J1") (pin "h40") (pinfunction "h40_h40") (pintype "bidirectional"))
    )
    (net (code "105") (name "unconnected-(J2-PadA1)") (class "Default")
      (node (ref "J2") (pin "A1") (pinfunction "A1_A1") (pintype "bidirectional"))
    )
    (net (code "106") (name "unconnected-(J2-PadA2)") (class "Default")
      (node (ref "J2") (pin "A2") (pinfunction "A2_A2") (pintype "bidirectional"))
    )
    (net (code "107") (name "unconnected-(J2-PadA7)") (class "Default")
      (node (ref "J2") (pin "A7") (pinfunction "A7_A7") (pintype "bidirectional"))
    )
    (net (code "108") (name "unconnected-(J2-PadA8)") (class "Default")
      (node (ref "J2") (pin "A8") (pinfunction "A8_A8") (pintype "bidirectional"))
    )
    (net (code "109") (name "unconnected-(J2-PadB1)") (class "Default")
      (node (ref "J2") (pin "B1") (pinfunction "B1_B1") (pintype "bidirectional"))
    )
    (net (code "110") (name "unconnected-(J2-PadB2)") (class "Default")
      (node (ref "J2") (pin "B2") (pinfunction "B2_B2") (pintype "bidirectional"))
    )
    (net (code "111") (name "unconnected-(J2-PadB3)") (class "Default")
      (node (ref "J2") (pin "B3") (pinfunction "B3_B3") (pintype "bidirectional"))
    )
    (net (code "112") (name "unconnected-(J2-PadB7)") (class "Default")
      (node (ref "J2") (pin "B7") (pinfunction "B7_B7") (pintype "bidirectional"))
    )
    (net (code "113") (name "unconnected-(J2-PadB8)") (class "Default")
      (node (ref "J2") (pin "B8") (pinfunction "B8_B8") (pintype "bidirectional"))
    )
    (net (code "114") (name "unconnected-(J2-PadC1)") (class "Default")
      (node (ref "J2") (pin "C1") (pinfunction "C1_C1") (pintype "bidirectional"))
    )
    (net (code "115") (name "unconnected-(J2-PadC2)") (class "Default")
      (node (ref "J2") (pin "C2") (pinfunction "C2_C2") (pintype "bidirectional"))
    )
    (net (code "116") (name "unconnected-(J2-PadC3)") (class "Default")
      (node (ref "J2") (pin "C3") (pinfunction "C3_C3") (pintype "bidirectional"))
    )
    (net (code "117") (name "unconnected-(J2-PadC4)") (class "Default")
      (node (ref "J2") (pin "C4") (pinfunction "C4_C4") (pintype "bidirectional"))
    )
    (net (code "118") (name "unconnected-(J2-PadC5)") (class "Default")
      (node (ref "J2") (pin "C5") (pinfunction "C5_C5") (pintype "bidirectional"))
    )
    (net (code "119") (name "unconnected-(J2-PadC6)") (class "Default")
      (node (ref "J2") (pin "C6") (pinfunction "C6_C6") (pintype "bidirectional"))
    )
    (net (code "120") (name "unconnected-(J2-PadC7)") (class "Default")
      (node (ref "J2") (pin "C7") (pinfunction "C7_C7") (pintype "bidirectional"))
    )
    (net (code "121") (name "unconnected-(J2-PadC8)") (class "Default")
      (node (ref "J2") (pin "C8") (pinfunction "C8_C8") (pintype "bidirectional"))
    )
    (net (code "122") (name "unconnected-(J2-PadC9)") (class "Default")
      (node (ref "J2") (pin "C9") (pinfunction "C9_C9") (pintype "bidirectional"))
    )
    (net (code "123") (name "unconnected-(J2-PadC10)") (class "Default")
      (node (ref "J2") (pin "C10") (pinfunction "C10_C10") (pintype "bidirectional"))
    )
    (net (code "124") (name "unconnected-(J2-PadD1)") (class "Default")
      (node (ref "J2") (pin "D1") (pinfunction "D1_D1") (pintype "bidirectional"))
    )
    (net (code "125") (name "unconnected-(J2-PadD2)") (class "Default")
      (node (ref "J2") (pin "D2") (pinfunction "D2_D2") (pintype "bidirectional"))
    )
    (net (code "126") (name "unconnected-(J2-PadD3)") (class "Default")
      (node (ref "J2") (pin "D3") (pinfunction "D3_D3") (pintype "bidirectional"))
    )
    (net (code "127") (name "unconnected-(J2-PadD4)") (class "Default")
      (node (ref "J2") (pin "D4") (pinfunction "D4_D4") (pintype "bidirectional"))
    )
    (net (code "128") (name "unconnected-(J2-PadD5)") (class "Default")
      (node (ref "J2") (pin "D5") (pinfunction "D5_D5") (pintype "bidirectional"))
    )
    (net (code "129") (name "unconnected-(J2-PadD6)") (class "Default")
      (node (ref "J2") (pin "D6") (pinfunction "D6_D6") (pintype "bidirectional"))
    )
    (net (code "130") (name "unconnected-(J2-PadD7)") (class "Default")
      (node (ref "J2") (pin "D7") (pinfunction "D7_D7") (pintype "bidirectional"))
    )
    (net (code "131") (name "unconnected-(J2-PadD8)") (class "Default")
      (node (ref "J2") (pin "D8") (pinfunction "D8_D8") (pintype "bidirectional"))
    )
    (net (code "132") (name "unconnected-(J2-PadD9)") (class "Default")
      (node (ref "J2") (pin "D9") (pinfunction "D9_D9") (pintype "bidirectional"))
    )
    (net (code "133") (name "unconnected-(J2-PadD10)") (class "Default")
      (node (ref "J2") (pin "D10") (pinfunction "D10_D10") (pintype "bidirectional"))
    )
    (net (code "134") (name "unconnected-(U1-A1-Pad1)") (class "Default")
      (node (ref "U1") (pin "1") (pinfunction "A1_1") (pintype "bidirectional"))
    )
    (net (code "135") (name "unconnected-(U1-B1-Pad20)") (class "Default")
      (node (ref "U1") (pin "20") (pinfunction "B1_20") (pintype "bidirectional"))
    )
  )
)
